# design.net
KiCad netlist of a schematic drawn in Altium Designer
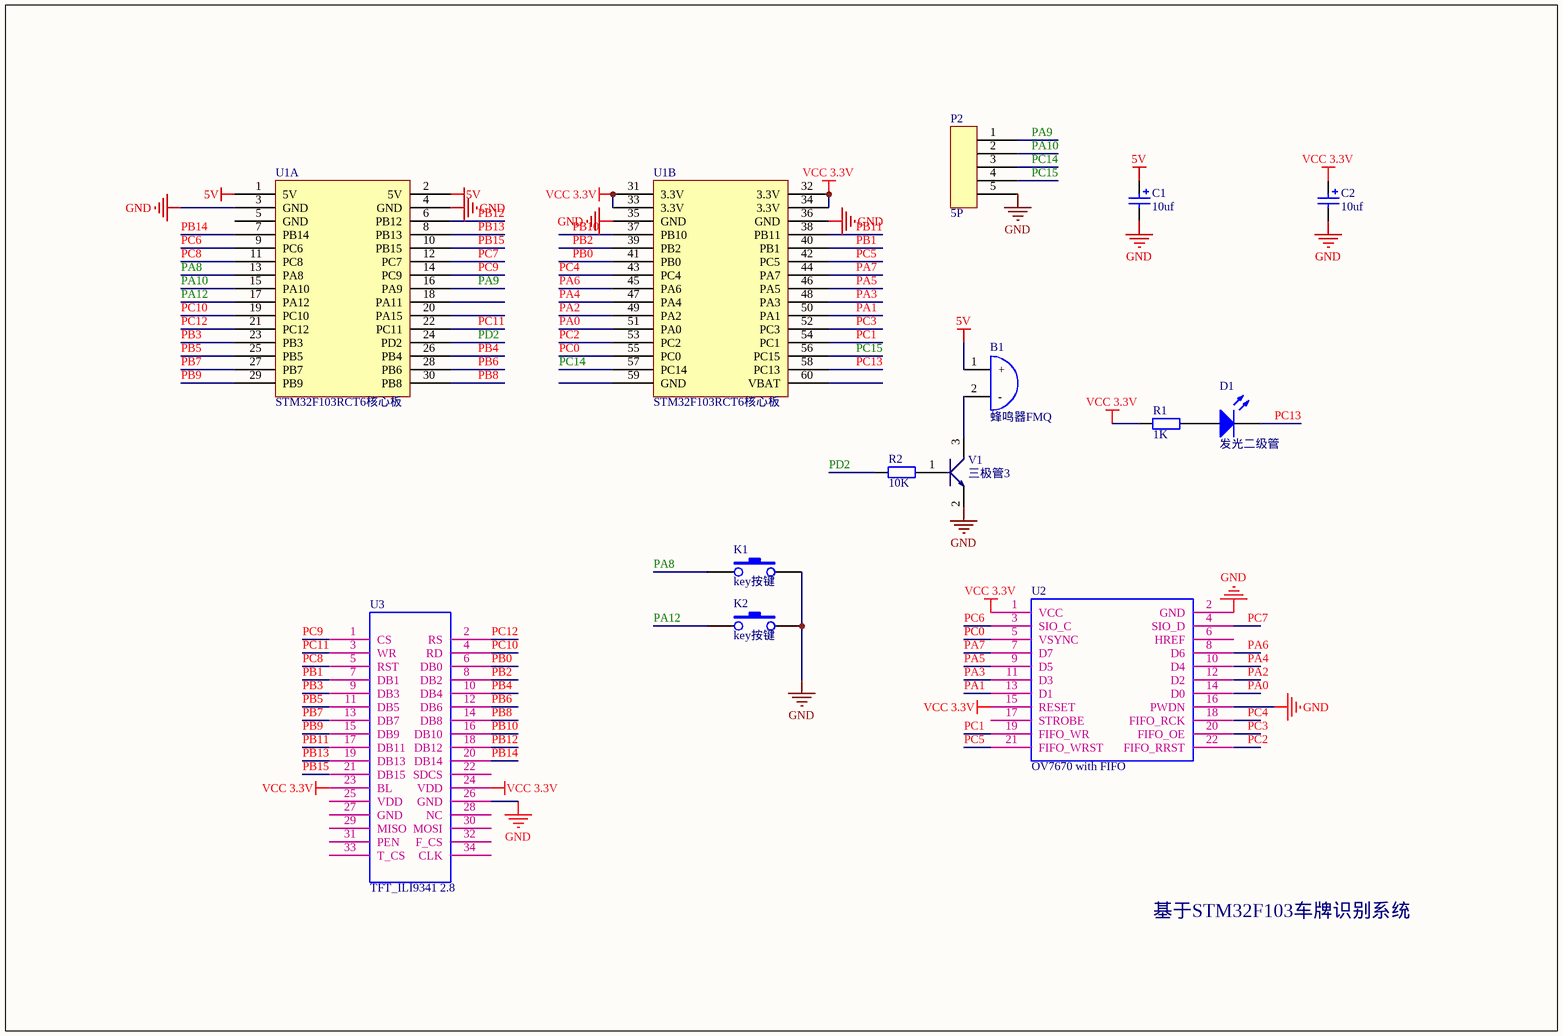
[diagram p0: 原理图（源文件格式）.SchDoc]

(export (version "E")
  (design (tool "Eeschema 10.0.6"))
  (components
    (comp (ref "B1") (value "蜂鸣器FMQ") (footprint "蜂鸣器") (libsource (lib "单片机1") (part "蜂鸣器FMQ")))
    (comp (ref "C1") (value "10uf") (footprint "CD0.254cm") (libsource (lib "单片机1") (part "电解电容")))
    (comp (ref "C2") (value "10uf") (footprint "CD0.254cm") (libsource (lib "单片机1") (part "电解电容")))
    (comp (ref "D1") (value "发光二级管") (footprint "发光二极管FZ") (libsource (lib "单片机1") (part "发光二级管")))
    (comp (ref "K1") (value "key按键") (footprint "按键") (libsource (lib "单片机1") (part "key按键")))
    (comp (ref "K2") (value "key按键") (footprint "按键") (libsource (lib "单片机1") (part "key按键")))
    (comp (ref "P2") (value "5P") (footprint "5ZHEN-100mil") (libsource (lib "各种接插件") (part "5P")))
    (comp (ref "R1") (value "1K") (footprint "电阻FZ") (libsource (lib "单片机1") (part "电阻R")))
    (comp (ref "R2") (value "10K") (footprint "电阻FZ") (libsource (lib "单片机1") (part "电阻R")))
    (comp (ref "U1")
      (value "STM32F103RCT6核心板")
      (footprint "STM32F103RC/RB 核心板")
      (libsource (lib "单片机1") (part "STM32F103RCT6核心板"))
    )
    (comp (ref "U2")
      (value "OV7670 with FIFO")
      (footprint "OV7670模块")
      (description "FIFO")
      (fields (field (name "PUBLISHER") "Altium Limited"))
      (libsource (lib "骑飞OV7670摄像头模块") (part "OV7670"))
    )
    (comp (ref "U3")
      (value "TFT_ILI9341 2.8")
      (footprint "2.8寸TFT")
      (description "ILI9341")
      (fields (field (name "PUBLISHER") "Altium Limited"))
      (libsource (lib "ILI9341彩屏") (part "TFT"))
    )
    (comp (ref "V1") (value "三极管3") (footprint "三极管FZ") (libsource (lib "单片机1") (part "三极管3")))
  )
  (nets
    (net (code "1") (name "/PA0") (class "Default")
      (node (ref "U1") (pin "51") (pinfunction "PA0_51") (pintype "passive"))
      (node (ref "U2") (pin "14") (pinfunction "D0_14") (pintype "passive"))
    )
    (net (code "2") (name "/PA1") (class "Default")
      (node (ref "U1") (pin "50") (pinfunction "PA1_50") (pintype "passive"))
      (node (ref "U2") (pin "13") (pinfunction "D1_13") (pintype "passive"))
    )
    (net (code "3") (name "/PA2") (class "Default")
      (node (ref "U1") (pin "49") (pinfunction "PA2_49") (pintype "passive"))
      (node (ref "U2") (pin "12") (pinfunction "D2_12") (pintype "passive"))
    )
    (net (code "4") (name "/PA3") (class "Default")
      (node (ref "U1") (pin "48") (pinfunction "PA3_48") (pintype "passive"))
      (node (ref "U2") (pin "11") (pinfunction "D3_11") (pintype "passive"))
    )
    (net (code "5") (name "/PA4") (class "Default")
      (node (ref "U1") (pin "47") (pinfunction "PA4_47") (pintype "passive"))
      (node (ref "U2") (pin "10") (pinfunction "D4_10") (pintype "passive"))
    )
    (net (code "6") (name "/PA5") (class "Default")
      (node (ref "U1") (pin "46") (pinfunction "PA5_46") (pintype "passive"))
      (node (ref "U2") (pin "9") (pinfunction "D5_9") (pintype "passive"))
    )
    (net (code "7") (name "/PA6") (class "Default")
      (node (ref "U1") (pin "45") (pinfunction "PA6_45") (pintype "passive"))
      (node (ref "U2") (pin "8") (pinfunction "D6_8") (pintype "passive"))
    )
    (net (code "8") (name "/PA7") (class "Default")
      (node (ref "U1") (pin "44") (pinfunction "PA7_44") (pintype "passive"))
      (node (ref "U2") (pin "7") (pinfunction "D7_7") (pintype "passive"))
    )
    (net (code "9") (name "/PA8") (class "Default")
      (node (ref "K1") (pin "1") (pinfunction "1_1") (pintype "passive"))
      (node (ref "U1") (pin "13") (pinfunction "PA8_13") (pintype "passive"))
    )
    (net (code "10") (name "/PA9") (class "Default")
      (node (ref "P2") (pin "1") (pinfunction "1_1") (pintype "passive"))
      (node (ref "U1") (pin "16") (pinfunction "PA9_16") (pintype "passive"))
    )
    (net (code "11") (name "/PA10") (class "Default")
      (node (ref "P2") (pin "2") (pinfunction "2_2") (pintype "passive"))
      (node (ref "U1") (pin "15") (pinfunction "PA10_15") (pintype "passive"))
    )
    (net (code "12") (name "/PA12") (class "Default")
      (node (ref "K2") (pin "1") (pinfunction "1_1") (pintype "passive"))
      (node (ref "U1") (pin "17") (pinfunction "PA12_17") (pintype "passive"))
    )
    (net (code "13") (name "/PB0") (class "Default")
      (node (ref "U1") (pin "41") (pinfunction "PB0_41") (pintype "passive"))
      (node (ref "U3") (pin "6") (pinfunction "DB0_6") (pintype "passive"))
    )
    (net (code "14") (name "/PB1") (class "Default")
      (node (ref "U1") (pin "40") (pinfunction "PB1_40") (pintype "passive"))
      (node (ref "U3") (pin "7") (pinfunction "DB1_7") (pintype "passive"))
    )
    (net (code "15") (name "/PB2") (class "Default")
      (node (ref "U1") (pin "39") (pinfunction "PB2_39") (pintype "passive"))
      (node (ref "U3") (pin "8") (pinfunction "DB2_8") (pintype "passive"))
    )
    (net (code "16") (name "/PB3") (class "Default")
      (node (ref "U1") (pin "23") (pinfunction "PB3_23") (pintype "passive"))
      (node (ref "U3") (pin "9") (pinfunction "DB3_9") (pintype "passive"))
    )
    (net (code "17") (name "/PB4") (class "Default")
      (node (ref "U1") (pin "26") (pinfunction "PB4_26") (pintype "passive"))
      (node (ref "U3") (pin "10") (pinfunction "DB4_10") (pintype "passive"))
    )
    (net (code "18") (name "/PB5") (class "Default")
      (node (ref "U1") (pin "25") (pinfunction "PB5_25") (pintype "passive"))
      (node (ref "U3") (pin "11") (pinfunction "DB5_11") (pintype "passive"))
    )
    (net (code "19") (name "/PB6") (class "Default")
      (node (ref "U1") (pin "28") (pinfunction "PB6_28") (pintype "passive"))
      (node (ref "U3") (pin "12") (pinfunction "DB6_12") (pintype "passive"))
    )
    (net (code "20") (name "/PB7") (class "Default")
      (node (ref "U1") (pin "27") (pinfunction "PB7_27") (pintype "passive"))
      (node (ref "U3") (pin "13") (pinfunction "DB7_13") (pintype "passive"))
    )
    (net (code "21") (name "/PB8") (class "Default")
      (node (ref "U1") (pin "30") (pinfunction "PB8_30") (pintype "passive"))
      (node (ref "U3") (pin "14") (pinfunction "DB8_14") (pintype "passive"))
    )
    (net (code "22") (name "/PB9") (class "Default")
      (node (ref "U1") (pin "29") (pinfunction "PB9_29") (pintype "passive"))
      (node (ref "U3") (pin "15") (pinfunction "DB9_15") (pintype "passive"))
    )
    (net (code "23") (name "/PB10") (class "Default")
      (node (ref "U1") (pin "37") (pinfunction "PB10_37") (pintype "passive"))
      (node (ref "U3") (pin "16") (pinfunction "DB10_16") (pintype "passive"))
    )
    (net (code "24") (name "/PB11") (class "Default")
      (node (ref "U1") (pin "38") (pinfunction "PB11_38") (pintype "passive"))
      (node (ref "U3") (pin "17") (pinfunction "DB11_17") (pintype "passive"))
    )
    (net (code "25") (name "/PB12") (class "Default")
      (node (ref "U1") (pin "6") (pinfunction "PB12_6") (pintype "passive"))
      (node (ref "U3") (pin "18") (pinfunction "DB12_18") (pintype "passive"))
    )
    (net (code "26") (name "/PB13") (class "Default")
      (node (ref "U1") (pin "8") (pinfunction "PB13_8") (pintype "passive"))
      (node (ref "U3") (pin "19") (pinfunction "DB13_19") (pintype "passive"))
    )
    (net (code "27") (name "/PB14") (class "Default")
      (node (ref "U1") (pin "7") (pinfunction "PB14_7") (pintype "passive"))
      (node (ref "U3") (pin "20") (pinfunction "DB14_20") (pintype "passive"))
    )
    (net (code "28") (name "/PB15") (class "Default")
      (node (ref "U1") (pin "10") (pinfunction "PB15_10") (pintype "passive"))
      (node (ref "U3") (pin "21") (pinfunction "DB15_21") (pintype "passive"))
    )
    (net (code "29") (name "/PC0") (class "Default")
      (node (ref "U1") (pin "55") (pinfunction "PC0_55") (pintype "passive"))
      (node (ref "U2") (pin "5") (pinfunction "VSYNC_5") (pintype "passive"))
    )
    (net (code "30") (name "/PC1") (class "Default")
      (node (ref "U1") (pin "54") (pinfunction "PC1_54") (pintype "passive"))
      (node (ref "U2") (pin "19") (pinfunction "FIFO_WR_19") (pintype "passive"))
    )
    (net (code "31") (name "/PC2") (class "Default")
      (node (ref "U1") (pin "53") (pinfunction "PC2_53") (pintype "passive"))
      (node (ref "U2") (pin "22") (pinfunction "FIFO_RRST_22") (pintype "passive"))
    )
    (net (code "32") (name "/PC3") (class "Default")
      (node (ref "U1") (pin "52") (pinfunction "PC3_52") (pintype "passive"))
      (node (ref "U2") (pin "20") (pinfunction "FIFO_OE_20") (pintype "passive"))
    )
    (net (code "33") (name "/PC4") (class "Default")
      (node (ref "U1") (pin "43") (pinfunction "PC4_43") (pintype "passive"))
      (node (ref "U2") (pin "18") (pinfunction "FIFO_RCK_18") (pintype "passive"))
    )
    (net (code "34") (name "/PC5") (class "Default")
      (node (ref "U1") (pin "42") (pinfunction "PC5_42") (pintype "passive"))
      (node (ref "U2") (pin "21") (pinfunction "FIFO_WRST_21") (pintype "passive"))
    )
    (net (code "35") (name "/PC6") (class "Default")
      (node (ref "U1") (pin "9") (pinfunction "PC6_9") (pintype "passive"))
      (node (ref "U2") (pin "3") (pinfunction "SIO_C_3") (pintype "passive"))
    )
    (net (code "36") (name "/PC7") (class "Default")
      (node (ref "U1") (pin "12") (pinfunction "PC7_12") (pintype "passive"))
      (node (ref "U2") (pin "4") (pinfunction "SIO_D_4") (pintype "passive"))
    )
    (net (code "37") (name "/PC8") (class "Default")
      (node (ref "U1") (pin "11") (pinfunction "PC8_11") (pintype "passive"))
      (node (ref "U3") (pin "5") (pinfunction "RST_5") (pintype "passive"))
    )
    (net (code "38") (name "/PC9") (class "Default")
      (node (ref "U1") (pin "14") (pinfunction "PC9_14") (pintype "passive"))
      (node (ref "U3") (pin "1") (pinfunction "CS_1") (pintype "passive"))
    )
    (net (code "39") (name "/PC10") (class "Default")
      (node (ref "U1") (pin "19") (pinfunction "PC10_19") (pintype "passive"))
      (node (ref "U3") (pin "4") (pinfunction "RD_4") (pintype "passive"))
    )
    (net (code "40") (name "/PC11") (class "Default")
      (node (ref "U1") (pin "22") (pinfunction "PC11_22") (pintype "passive"))
      (node (ref "U3") (pin "3") (pinfunction "WR_3") (pintype "passive"))
    )
    (net (code "41") (name "/PC12") (class "Default")
      (node (ref "U1") (pin "21") (pinfunction "PC12_21") (pintype "passive"))
      (node (ref "U3") (pin "2") (pinfunction "RS_2") (pintype "passive"))
    )
    (net (code "42") (name "/PC13") (class "Default")
      (node (ref "D1") (pin "2") (pinfunction "K_2") (pintype "passive"))
      (node (ref "U1") (pin "58") (pinfunction "PC13_58") (pintype "passive"))
    )
    (net (code "43") (name "/PC14") (class "Default")
      (node (ref "P2") (pin "3") (pinfunction "3_3") (pintype "passive"))
      (node (ref "U1") (pin "57") (pinfunction "PC14_57") (pintype "passive"))
    )
    (net (code "44") (name "/PC15") (class "Default")
      (node (ref "P2") (pin "4") (pinfunction "4_4") (pintype "passive"))
      (node (ref "U1") (pin "56") (pinfunction "PC15_56") (pintype "passive"))
    )
    (net (code "45") (name "/PD2") (class "Default")
      (node (ref "R2") (pin "1") (pinfunction "1_1") (pintype "passive"))
      (node (ref "U1") (pin "24") (pinfunction "PD2_24") (pintype "passive"))
    )
    (net (code "46") (name "5V") (class "Default")
      (node (ref "B1") (pin "1") (pinfunction "+_1") (pintype "passive"))
      (node (ref "C1") (pin "1") (pinfunction "1_1") (pintype "passive"))
      (node (ref "U1") (pin "1") (pinfunction "5V_1") (pintype "passive"))
      (node (ref "U1") (pin "2") (pinfunction "5V_2") (pintype "passive"))
    )
    (net (code "47") (name "GND") (class "Default")
      (node (ref "C1") (pin "2") (pinfunction "2_2") (pintype "passive"))
      (node (ref "C2") (pin "2") (pinfunction "2_2") (pintype "passive"))
      (node (ref "K1") (pin "2") (pinfunction "2_2") (pintype "passive"))
      (node (ref "K2") (pin "2") (pinfunction "2_2") (pintype "passive"))
      (node (ref "P2") (pin "5") (pinfunction "5_5") (pintype "passive"))
      (node (ref "U1") (pin "3") (pinfunction "GND_3") (pintype "passive"))
      (node (ref "U1") (pin "35") (pinfunction "GND_35") (pintype "passive"))
      (node (ref "U1") (pin "36") (pinfunction "GND_36") (pintype "passive"))
      (node (ref "U1") (pin "4") (pinfunction "GND_4") (pintype "passive"))
      (node (ref "U2") (pin "16") (pinfunction "PWDN_16") (pintype "passive"))
      (node (ref "U2") (pin "2") (pinfunction "GND_2") (pintype "passive"))
      (node (ref "U3") (pin "26") (pinfunction "GND_26") (pintype "passive"))
      (node (ref "V1") (pin "2") (pinfunction "2_2") (pintype "passive"))
    )
    (net (code "48") (name "Net-(B1--)") (class "Default")
      (node (ref "B1") (pin "2") (pinfunction "-_2") (pintype "passive"))
      (node (ref "V1") (pin "3") (pinfunction "3_3") (pintype "passive"))
    )
    (net (code "49") (name "Net-(D1-A)") (class "Default")
      (node (ref "D1") (pin "1") (pinfunction "A_1") (pintype "passive"))
      (node (ref "R1") (pin "2") (pinfunction "2_2") (pintype "passive"))
    )
    (net (code "50") (name "Net-(R2-Pad2)") (class "Default")
      (node (ref "R2") (pin "2") (pinfunction "2_2") (pintype "passive"))
      (node (ref "V1") (pin "1") (pinfunction "1_1") (pintype "passive"))
    )
    (net (code "51") (name "VCC 3.3V") (class "Default")
      (node (ref "C2") (pin "1") (pinfunction "1_1") (pintype "passive"))
      (node (ref "R1") (pin "1") (pinfunction "1_1") (pintype "passive"))
      (node (ref "U1") (pin "31") (pinfunction "3.3V_31") (pintype "passive"))
      (node (ref "U1") (pin "32") (pinfunction "3.3V_32") (pintype "passive"))
      (node (ref "U1") (pin "33") (pinfunction "3.3V_33") (pintype "passive"))
      (node (ref "U1") (pin "34") (pinfunction "3.3V_34") (pintype "passive"))
      (node (ref "U2") (pin "1") (pinfunction "VCC_1") (pintype "passive"))
      (node (ref "U2") (pin "15") (pinfunction "RESET_15") (pintype "passive"))
      (node (ref "U3") (pin "23") (pinfunction "BL_23") (pintype "passive"))
      (node (ref "U3") (pin "24") (pinfunction "VDD_24") (pintype "passive"))
    )
    (net (code "52") (name "unconnected-(U1A-GND-Pad5)") (class "Default")
      (node (ref "U1") (pin "5") (pinfunction "GND_5") (pintype "passive"))
    )
    (net (code "53") (name "unconnected-(U1A-PA11-Pad18)") (class "Default")
      (node (ref "U1") (pin "18") (pinfunction "PA11_18") (pintype "passive"))
    )
    (net (code "54") (name "unconnected-(U1A-PA15-Pad20)") (class "Default")
      (node (ref "U1") (pin "20") (pinfunction "PA15_20") (pintype "passive"))
    )
    (net (code "55") (name "unconnected-(U1B-GND-Pad59)") (class "Default")
      (node (ref "U1") (pin "59") (pinfunction "GND_59") (pintype "passive"))
    )
    (net (code "56") (name "unconnected-(U1B-VBAT-Pad60)") (class "Default")
      (node (ref "U1") (pin "60") (pinfunction "VBAT_60") (pintype "passive"))
    )
    (net (code "57") (name "unconnected-(U2-HREF-Pad6)") (class "Default")
      (node (ref "U2") (pin "6") (pinfunction "HREF_6") (pintype "passive"))
    )
    (net (code "58") (name "unconnected-(U2-STROBE-Pad17)") (class "Default")
      (node (ref "U2") (pin "17") (pinfunction "STROBE_17") (pintype "passive"))
    )
    (net (code "59") (name "unconnected-(U3-CLK-Pad34)") (class "Default")
      (node (ref "U3") (pin "34") (pinfunction "CLK_34") (pintype "passive"))
    )
    (net (code "60") (name "unconnected-(U3-F_CS-Pad32)") (class "Default")
      (node (ref "U3") (pin "32") (pinfunction "F_CS_32") (pintype "passive"))
    )
    (net (code "61") (name "unconnected-(U3-GND-Pad27)") (class "Default")
      (node (ref "U3") (pin "27") (pinfunction "GND_27") (pintype "passive"))
    )
    (net (code "62") (name "unconnected-(U3-MISO-Pad29)") (class "Default")
      (node (ref "U3") (pin "29") (pinfunction "MISO_29") (pintype "passive"))
    )
    (net (code "63") (name "unconnected-(U3-MOSI-Pad30)") (class "Default")
      (node (ref "U3") (pin "30") (pinfunction "MOSI_30") (pintype "passive"))
    )
    (net (code "64") (name "unconnected-(U3-NC-Pad28)") (class "Default")
      (node (ref "U3") (pin "28") (pinfunction "NC_28") (pintype "passive"))
    )
    (net (code "65") (name "unconnected-(U3-PEN-Pad31)") (class "Default")
      (node (ref "U3") (pin "31") (pinfunction "PEN_31") (pintype "passive"))
    )
    (net (code "66") (name "unconnected-(U3-SDCS-Pad22)") (class "Default")
      (node (ref "U3") (pin "22") (pinfunction "SDCS_22") (pintype "passive"))
    )
    (net (code "67") (name "unconnected-(U3-T_CS-Pad33)") (class "Default")
      (node (ref "U3") (pin "33") (pinfunction "T_CS_33") (pintype "passive"))
    )
    (net (code "68") (name "unconnected-(U3-VDD-Pad25)") (class "Default")
      (node (ref "U3") (pin "25") (pinfunction "VDD_25") (pintype "passive"))
    )
  )
)
